# analogPath.net
KiCad netlist of a schematic drawn in Altium Designer
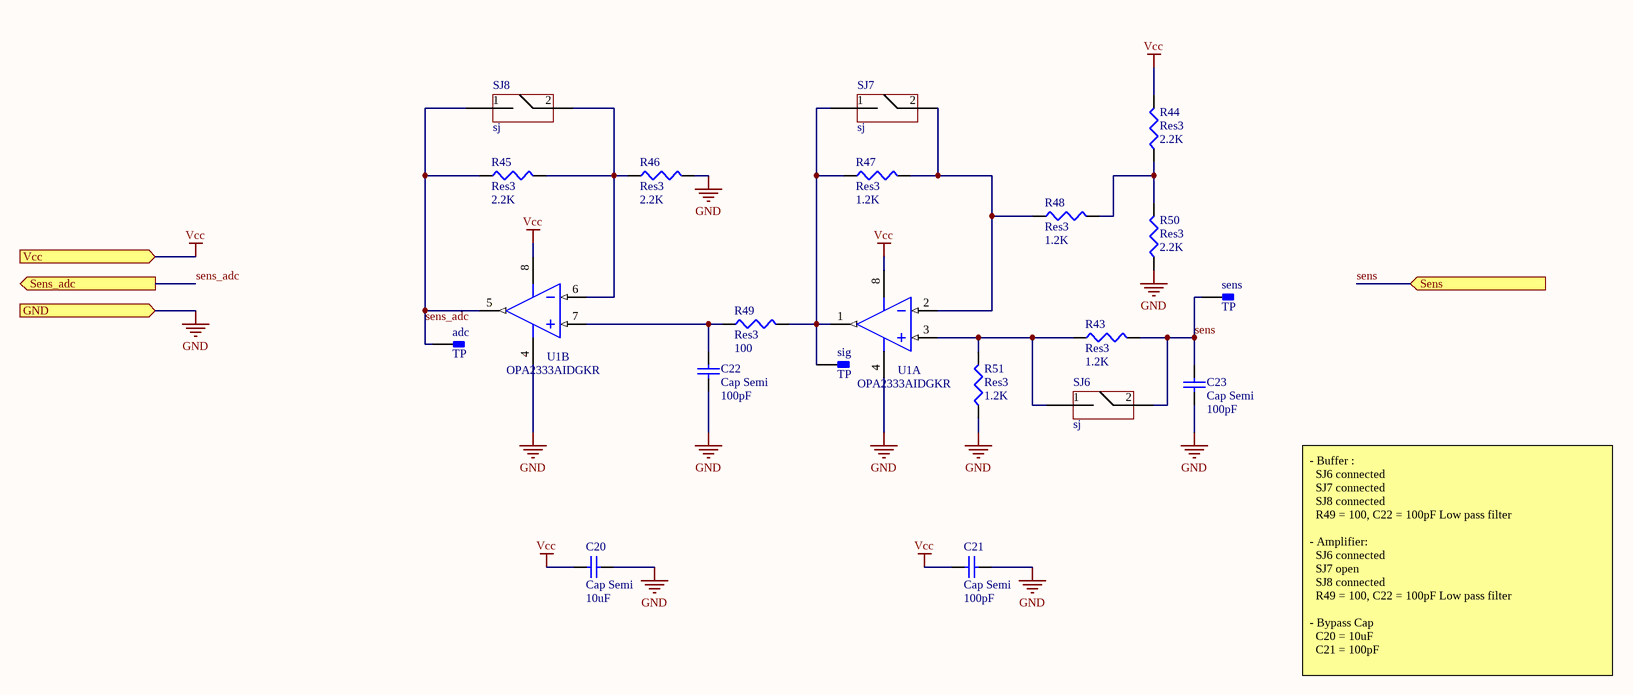
[diagram p0: analogPath.SchDoc]

(export (version "E")
  (design (tool "Eeschema 10.0.6"))
  (components
    (comp (ref "adc")
      (value "TP")
      (footprint "TP")
      (description "Solder test point")
      (libsource (lib "IoWLabs") (part "TP"))
    )
    (comp (ref "C20")
      (value "Cap Semi")
      (footprint "1608[0603]")
      (description "Capacitor (Semiconductor SIM Model)")
      (fields
        (field (name "ALTIUM_VALUE") "10uF")
        (field (name "MANUFACTURER") "Samsung Electro-Mechanics")
        (field (name "MANUFACTURER PART NUMBER") "CL10A106MQ8NNNC")
        (field (name "PUBLISHER") "Altium Limited")
      )
      (libsource (lib "Miscellaneous Devices") (part "Cap Semi"))
    )
    (comp (ref "C21")
      (value "Cap Semi")
      (footprint "1608[0603]")
      (description "Capacitor (Semiconductor SIM Model)")
      (fields
        (field (name "ALTIUM_VALUE") "100pF")
        (field (name "MANUFACTURER") "YAGEO")
        (field (name "MANUFACTURER PART NUMBER") "CC0603KRX7R9BB1")
        (field (name "PUBLISHER") "Altium Limited")
      )
      (libsource (lib "Miscellaneous Devices") (part "Cap Semi"))
    )
    (comp (ref "C22")
      (value "Cap Semi")
      (footprint "1608[0603]")
      (description "Capacitor (Semiconductor SIM Model)")
      (fields
        (field (name "ALTIUM_VALUE") "100pF")
        (field (name "MANUFACTURER") "YAGEO")
        (field (name "MANUFACTURER PART NUMBER") "CC0603KRX7R9BB101")
        (field (name "PUBLISHER") "Altium Limited")
      )
      (libsource (lib "Miscellaneous Devices") (part "Cap Semi"))
    )
    (comp (ref "C23")
      (value "Cap Semi")
      (footprint "1608[0603]")
      (description "Capacitor (Semiconductor SIM Model)")
      (fields
        (field (name "ALTIUM_VALUE") "100pF")
        (field (name "MANUFACTURER") "YAGEO")
        (field (name "MANUFACTURER PART NUMBER") "CC0603KRX7R9BB1")
        (field (name "PUBLISHER") "Altium Limited")
      )
      (libsource (lib "Miscellaneous Devices") (part "Cap Semi"))
    )
    (comp (ref "R43")
      (value "Res3")
      (footprint "J1-0603")
      (description "Resistor")
      (fields
        (field (name "ALTIUM_VALUE") "1.2K")
        (field (name "MANUFACTURER PART NUMBER") "MCR03EZPFX1201")
        (field (name "MANUFACTURER") "ROHM Semicon")
        (field (name "PUBLISHER") "Altium Limited")
      )
      (libsource (lib "Miscellaneous Devices") (part "Res3"))
    )
    (comp (ref "R44")
      (value "Res3")
      (footprint "J1-0603")
      (description "Resistor")
      (fields
        (field (name "ALTIUM_VALUE") "2.2K")
        (field (name "MANUFACTURER PART NUMBER") "RC0603FR-072K2L")
        (field (name "MANUFACTURER") "YAGEO")
        (field (name "PUBLISHER") "Altium Limited")
      )
      (libsource (lib "Miscellaneous Devices") (part "Res3"))
    )
    (comp (ref "R45")
      (value "Res3")
      (footprint "J1-0603")
      (description "Resistor")
      (fields
        (field (name "ALTIUM_VALUE") "2.2K")
        (field (name "MANUFACTURER PART NUMBER") "RC0603FR-072K2L")
        (field (name "MANUFACTURER") "YAGEO")
        (field (name "PUBLISHER") "Altium Limited")
      )
      (libsource (lib "Miscellaneous Devices") (part "Res3"))
    )
    (comp (ref "R46")
      (value "Res3")
      (footprint "J1-0603")
      (description "Resistor")
      (fields
        (field (name "ALTIUM_VALUE") "2.2K")
        (field (name "MANUFACTURER PART NUMBER") "RC0603FR-072K2L")
        (field (name "MANUFACTURER") "YAGEO")
        (field (name "PUBLISHER") "Altium Limited")
      )
      (libsource (lib "Miscellaneous Devices") (part "Res3"))
    )
    (comp (ref "R47")
      (value "Res3")
      (footprint "J1-0603")
      (description "Resistor")
      (fields
        (field (name "ALTIUM_VALUE") "1.2K")
        (field (name "MANUFACTURER PART NUMBER") "MCR03EZPFX1201")
        (field (name "MANUFACTURER") "ROHM Semicon")
        (field (name "PUBLISHER") "Altium Limited")
      )
      (libsource (lib "Miscellaneous Devices") (part "Res3"))
    )
    (comp (ref "R48")
      (value "Res3")
      (footprint "J1-0603")
      (description "Resistor")
      (fields
        (field (name "ALTIUM_VALUE") "1.2K")
        (field (name "MANUFACTURER PART NUMBER") "MCR03EZPFX1201")
        (field (name "MANUFACTURER") "ROHM Semicon")
        (field (name "PUBLISHER") "Altium Limited")
      )
      (libsource (lib "Miscellaneous Devices") (part "Res3"))
    )
    (comp (ref "R49")
      (value "Res3")
      (footprint "J1-0603")
      (description "Resistor")
      (fields
        (field (name "ALTIUM_VALUE") "100")
        (field (name "MANUFACTURER PART NUMBER") "RC0603FR-07100RL")
        (field (name "MANUFACTURER") "YAGEO")
        (field (name "PUBLISHER") "Altium Limited")
      )
      (libsource (lib "Miscellaneous Devices") (part "Res3"))
    )
    (comp (ref "R50")
      (value "Res3")
      (footprint "J1-0603")
      (description "Resistor")
      (fields
        (field (name "ALTIUM_VALUE") "2.2K")
        (field (name "MANUFACTURER PART NUMBER") "RC0603FR-072K2L")
        (field (name "MANUFACTURER") "YAGEO")
        (field (name "PUBLISHER") "Altium Limited")
      )
      (libsource (lib "Miscellaneous Devices") (part "Res3"))
    )
    (comp (ref "R51")
      (value "Res3")
      (footprint "J1-0603")
      (description "Resistor")
      (fields
        (field (name "ALTIUM_VALUE") "1.2K")
        (field (name "MANUFACTURER PART NUMBER") "MCR03EZPFX1201")
        (field (name "MANUFACTURER") "ROHM Semicon")
        (field (name "PUBLISHER") "Altium Limited")
      )
      (libsource (lib "Miscellaneous Devices") (part "Res3"))
    )
    (comp (ref "sens")
      (value "TP")
      (footprint "TP")
      (description "Solder test point")
      (libsource (lib "IoWLabs") (part "TP"))
    )
    (comp (ref "sig")
      (value "TP")
      (footprint "TP")
      (description "Solder test point")
      (libsource (lib "IoWLabs") (part "TP"))
    )
    (comp (ref "SJ6")
      (value "sj")
      (footprint "SJ2")
      (description "solder jumper generic")
      (libsource (lib "IoWLabs") (part "Jumper"))
    )
    (comp (ref "SJ7")
      (value "sj")
      (footprint "SJ2")
      (description "solder jumper generic")
      (libsource (lib "IoWLabs") (part "Jumper"))
    )
    (comp (ref "SJ8")
      (value "sj")
      (footprint "SJ2")
      (description "solder jumper generic")
      (libsource (lib "IoWLabs") (part "Jumper"))
    )
    (comp (ref "U1")
      (value "OPA2333AIDGKR")
      (footprint "MSOP-8")
      (description "Precision OpAmps Zero-Drift 2 1.8V ~ 5.5V, ±0.9V ~ 2.75V 350kHz 0.16 V/us MSOP-8 RoHS")
      (fields (field (name "MANUFACTURER") "Texas Instruments"))
      (libsource (lib "") (part "OPA2333_1"))
    )
  )
  (nets
    (net (code "1") (name "/sens") (class "Default")
      (node (ref "C23") (pin "2") (pinfunction "2_2") (pintype "passive"))
      (node (ref "R43") (pin "2") (pinfunction "2_2") (pintype "passive"))
      (node (ref "SJ6") (pin "2") (pinfunction "2_2") (pintype "passive"))
      (node (ref "sens") (pin "1") (pinfunction "1_1") (pintype "passive"))
    )
    (net (code "2") (name "/sens_adc") (class "Default")
      (node (ref "R45") (pin "1") (pinfunction "1_1") (pintype "passive"))
      (node (ref "SJ8") (pin "1") (pinfunction "1_1") (pintype "passive"))
      (node (ref "U1") (pin "5") (pinfunction "OUT_A_5") (pintype "output"))
      (node (ref "adc") (pin "1") (pinfunction "1_1") (pintype "passive"))
    )
    (net (code "3") (name "GND") (class "Default")
      (node (ref "C20") (pin "1") (pinfunction "1_1") (pintype "passive"))
      (node (ref "C21") (pin "2") (pinfunction "2_2") (pintype "passive"))
      (node (ref "C22") (pin "1") (pinfunction "1_1") (pintype "passive"))
      (node (ref "C23") (pin "1") (pinfunction "1_1") (pintype "passive"))
      (node (ref "R46") (pin "2") (pinfunction "2_2") (pintype "passive"))
      (node (ref "R50") (pin "1") (pinfunction "1_1") (pintype "passive"))
      (node (ref "R51") (pin "1") (pinfunction "1_1") (pintype "passive"))
      (node (ref "U1") (pin "4") (pinfunction "-V_4") (pintype "passive"))
    )
    (net (code "4") (name "Net-(R44-Pad1)") (class "Default")
      (node (ref "R44") (pin "1") (pinfunction "1_1") (pintype "passive"))
      (node (ref "R48") (pin "2") (pinfunction "2_2") (pintype "passive"))
      (node (ref "R50") (pin "2") (pinfunction "2_2") (pintype "passive"))
    )
    (net (code "5") (name "Net-(U1A-+IN_A)") (class "Default")
      (node (ref "R43") (pin "1") (pinfunction "1_1") (pintype "passive"))
      (node (ref "R51") (pin "2") (pinfunction "2_2") (pintype "passive"))
      (node (ref "SJ6") (pin "1") (pinfunction "1_1") (pintype "passive"))
      (node (ref "U1") (pin "3") (pinfunction "+IN_A_3") (pintype "input"))
    )
    (net (code "6") (name "Net-(U1A--IN_A)") (class "Default")
      (node (ref "R47") (pin "2") (pinfunction "2_2") (pintype "passive"))
      (node (ref "R48") (pin "1") (pinfunction "1_1") (pintype "passive"))
      (node (ref "SJ7") (pin "2") (pinfunction "2_2") (pintype "passive"))
      (node (ref "U1") (pin "2") (pinfunction "-IN_A_2") (pintype "input"))
    )
    (net (code "7") (name "Net-(U1A-OUT_A)") (class "Default")
      (node (ref "R47") (pin "1") (pinfunction "1_1") (pintype "passive"))
      (node (ref "R49") (pin "2") (pinfunction "2_2") (pintype "passive"))
      (node (ref "SJ7") (pin "1") (pinfunction "1_1") (pintype "passive"))
      (node (ref "U1") (pin "1") (pinfunction "OUT_A_1") (pintype "output"))
      (node (ref "sig") (pin "1") (pinfunction "1_1") (pintype "passive"))
    )
    (net (code "8") (name "Net-(U1B-+IN_A)") (class "Default")
      (node (ref "C22") (pin "2") (pinfunction "2_2") (pintype "passive"))
      (node (ref "R49") (pin "1") (pinfunction "1_1") (pintype "passive"))
      (node (ref "U1") (pin "7") (pinfunction "+IN_A_7") (pintype "input"))
    )
    (net (code "9") (name "Net-(U1B--IN_A)") (class "Default")
      (node (ref "R45") (pin "2") (pinfunction "2_2") (pintype "passive"))
      (node (ref "R46") (pin "1") (pinfunction "1_1") (pintype "passive"))
      (node (ref "SJ8") (pin "2") (pinfunction "2_2") (pintype "passive"))
      (node (ref "U1") (pin "6") (pinfunction "-IN_A_6") (pintype "input"))
    )
    (net (code "10") (name "Vcc") (class "Default")
      (node (ref "C20") (pin "2") (pinfunction "2_2") (pintype "passive"))
      (node (ref "C21") (pin "1") (pinfunction "1_1") (pintype "passive"))
      (node (ref "R44") (pin "2") (pinfunction "2_2") (pintype "passive"))
      (node (ref "U1") (pin "8") (pinfunction "+V_8") (pintype "passive"))
    )
  )
)
